# PC_ParallelPort.net
KiCad netlist of a schematic drawn in Altium Designer
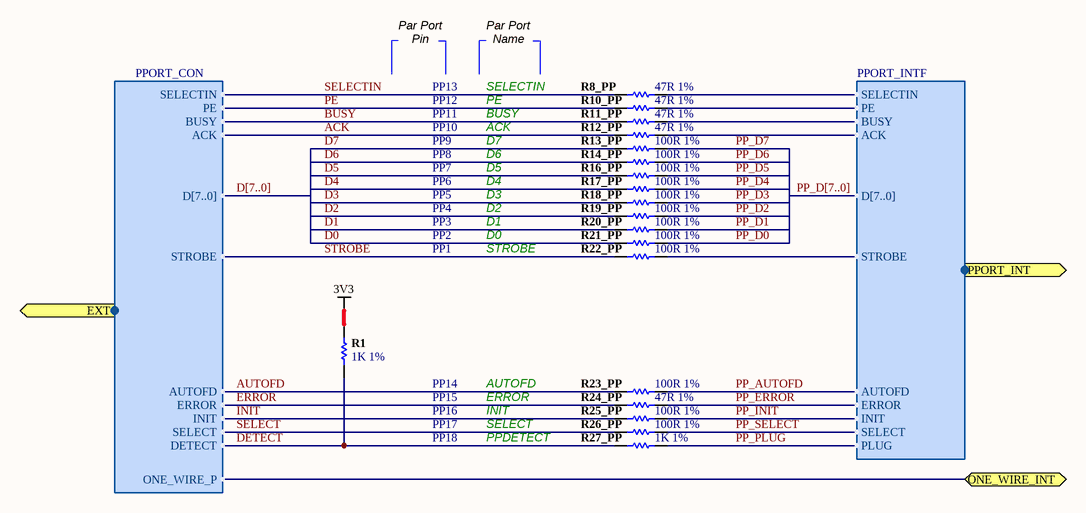
[diagram p0: PC_ParallelPort.SchDoc]

(export (version "E")
  (design (tool "Eeschema 10.0.6"))
  (components
    (comp (ref "R1")
      (value "1K 1%")
      (footprint "RESC1005-STAR")
      (description "Resistor, 1K 1% 0402 (1005)")
      (fields (field (name "TOLERANCE") "1 %"))
      (libsource (lib "AltiumDesignLibrary") (part "RES"))
    )
    (comp (ref "R8_PP")
      (value "47R 1%")
      (footprint "RESC1005-STAR")
      (description "Resistor, 47R 1% 0402 (1005)")
      (fields (field (name "TOLERANCE") "1 %"))
      (libsource (lib "AltiumDesignLibrary") (part "RES"))
    )
    (comp (ref "R10_PP")
      (value "47R 1%")
      (footprint "RESC1005-STAR")
      (description "Resistor, 47R 1% 0402 (1005)")
      (fields (field (name "TOLERANCE") "1 %"))
      (libsource (lib "AltiumDesignLibrary") (part "RES"))
    )
    (comp (ref "R11_PP")
      (value "47R 1%")
      (footprint "RESC1005-STAR")
      (description "Resistor, 47R 1% 0402 (1005)")
      (fields (field (name "TOLERANCE") "1 %"))
      (libsource (lib "AltiumDesignLibrary") (part "RES"))
    )
    (comp (ref "R12_PP")
      (value "47R 1%")
      (footprint "RESC1005-STAR")
      (description "Resistor, 47R 1% 0402 (1005)")
      (fields (field (name "TOLERANCE") "1 %"))
      (libsource (lib "AltiumDesignLibrary") (part "RES"))
    )
    (comp (ref "R13_PP")
      (value "100R 1%")
      (footprint "RESC1005-STAR")
      (description "Resistor, 100R 1% 0402 (1005)")
      (fields (field (name "TOLERANCE") "1 %"))
      (libsource (lib "AltiumDesignLibrary") (part "RES"))
    )
    (comp (ref "R14_PP")
      (value "100R 1%")
      (footprint "RESC1005-STAR")
      (description "Resistor, 100R 1% 0402 (1005)")
      (fields (field (name "TOLERANCE") "1 %"))
      (libsource (lib "AltiumDesignLibrary") (part "RES"))
    )
    (comp (ref "R16_PP")
      (value "100R 1%")
      (footprint "RESC1005-STAR")
      (description "Resistor, 100R 1% 0402 (1005)")
      (fields (field (name "TOLERANCE") "1 %"))
      (libsource (lib "AltiumDesignLibrary") (part "RES"))
    )
    (comp (ref "R17_PP")
      (value "100R 1%")
      (footprint "RESC1005-STAR")
      (description "Resistor, 100R 1% 0402 (1005)")
      (fields (field (name "TOLERANCE") "1 %"))
      (libsource (lib "AltiumDesignLibrary") (part "RES"))
    )
    (comp (ref "R18_PP")
      (value "100R 1%")
      (footprint "RESC1005-STAR")
      (description "Resistor, 100R 1% 0402 (1005)")
      (fields (field (name "TOLERANCE") "1 %"))
      (libsource (lib "AltiumDesignLibrary") (part "RES"))
    )
    (comp (ref "R19_PP")
      (value "100R 1%")
      (footprint "RESC1005-STAR")
      (description "Resistor, 100R 1% 0402 (1005)")
      (fields (field (name "TOLERANCE") "1 %"))
      (libsource (lib "AltiumDesignLibrary") (part "RES"))
    )
    (comp (ref "R20_PP")
      (value "100R 1%")
      (footprint "RESC1005-STAR")
      (description "Resistor, 100R 1% 0402 (1005)")
      (fields (field (name "TOLERANCE") "1 %"))
      (libsource (lib "AltiumDesignLibrary") (part "RES"))
    )
    (comp (ref "R21_PP")
      (value "100R 1%")
      (footprint "RESC1005-STAR")
      (description "Resistor, 100R 1% 0402 (1005)")
      (fields (field (name "TOLERANCE") "1 %"))
      (libsource (lib "AltiumDesignLibrary") (part "RES"))
    )
    (comp (ref "R22_PP")
      (value "100R 1%")
      (footprint "RESC1005-STAR")
      (description "Resistor, 100R 1% 0402 (1005)")
      (fields (field (name "TOLERANCE") "1 %"))
      (libsource (lib "AltiumDesignLibrary") (part "RES"))
    )
    (comp (ref "R23_PP")
      (value "100R 1%")
      (footprint "RESC1005-STAR")
      (description "Resistor, 100R 1% 0402 (1005)")
      (fields (field (name "TOLERANCE") "1 %"))
      (libsource (lib "AltiumDesignLibrary") (part "RES"))
    )
    (comp (ref "R24_PP")
      (value "47R 1%")
      (footprint "RESC1005-STAR")
      (description "Resistor, 47R 1% 0402 (1005)")
      (fields (field (name "TOLERANCE") "1 %"))
      (libsource (lib "AltiumDesignLibrary") (part "RES"))
    )
    (comp (ref "R25_PP")
      (value "100R 1%")
      (footprint "RESC1005-STAR")
      (description "Resistor, 100R 1% 0402 (1005)")
      (fields (field (name "TOLERANCE") "1 %"))
      (libsource (lib "AltiumDesignLibrary") (part "RES"))
    )
    (comp (ref "R26_PP")
      (value "100R 1%")
      (footprint "RESC1005-STAR")
      (description "Resistor, 100R 1% 0402 (1005)")
      (fields (field (name "TOLERANCE") "1 %"))
      (libsource (lib "AltiumDesignLibrary") (part "RES"))
    )
    (comp (ref "R27_PP")
      (value "1K 1%")
      (footprint "RESC1005-STAR")
      (description "Resistor, 1K 1% 0402 (1005)")
      (fields (field (name "TOLERANCE") "1 %"))
      (libsource (lib "AltiumDesignLibrary") (part "RES"))
    )
  )
  (nets
    (net (code "3") (name "/ACK") (class "Default")
      (node (ref "R12_PP") (pin "1") (pinfunction "1_1") (pintype "passive"))
    )
    (net (code "4") (name "/AUTOFD") (class "Default")
      (node (ref "R23_PP") (pin "2") (pinfunction "2_2") (pintype "passive"))
    )
    (net (code "5") (name "/BUSY") (class "Default")
      (node (ref "R11_PP") (pin "1") (pinfunction "1_1") (pintype "passive"))
    )
    (net (code "6") (name "/D0") (class "Default")
      (node (ref "R21_PP") (pin "2") (pinfunction "2_2") (pintype "passive"))
    )
    (net (code "7") (name "/D1") (class "Default")
      (node (ref "R20_PP") (pin "2") (pinfunction "2_2") (pintype "passive"))
    )
    (net (code "8") (name "/D2") (class "Default")
      (node (ref "R19_PP") (pin "2") (pinfunction "2_2") (pintype "passive"))
    )
    (net (code "9") (name "/D3") (class "Default")
      (node (ref "R18_PP") (pin "2") (pinfunction "2_2") (pintype "passive"))
    )
    (net (code "10") (name "/D4") (class "Default")
      (node (ref "R17_PP") (pin "2") (pinfunction "2_2") (pintype "passive"))
    )
    (net (code "11") (name "/D5") (class "Default")
      (node (ref "R16_PP") (pin "2") (pinfunction "2_2") (pintype "passive"))
    )
    (net (code "12") (name "/D6") (class "Default")
      (node (ref "R14_PP") (pin "2") (pinfunction "2_2") (pintype "passive"))
    )
    (net (code "13") (name "/D7") (class "Default")
      (node (ref "R13_PP") (pin "2") (pinfunction "2_2") (pintype "passive"))
    )
    (net (code "14") (name "/DETECT") (class "Default")
      (node (ref "R1") (pin "1") (pinfunction "1_1") (pintype "passive"))
      (node (ref "R27_PP") (pin "2") (pinfunction "2_2") (pintype "passive"))
    )
    (net (code "15") (name "/ERROR") (class "Default")
      (node (ref "R24_PP") (pin "1") (pinfunction "1_1") (pintype "passive"))
    )
    (net (code "17") (name "/INIT") (class "Default")
      (node (ref "R25_PP") (pin "2") (pinfunction "2_2") (pintype "passive"))
    )
    (net (code "19") (name "/PE") (class "Default")
      (node (ref "R10_PP") (pin "1") (pinfunction "1_1") (pintype "passive"))
    )
    (net (code "21") (name "/PP_AUTOFD") (class "Default")
      (node (ref "R23_PP") (pin "1") (pinfunction "1_1") (pintype "passive"))
    )
    (net (code "22") (name "/PP_D0") (class "Default")
      (node (ref "R21_PP") (pin "1") (pinfunction "1_1") (pintype "passive"))
    )
    (net (code "23") (name "/PP_D1") (class "Default")
      (node (ref "R20_PP") (pin "1") (pinfunction "1_1") (pintype "passive"))
    )
    (net (code "24") (name "/PP_D2") (class "Default")
      (node (ref "R19_PP") (pin "1") (pinfunction "1_1") (pintype "passive"))
    )
    (net (code "25") (name "/PP_D3") (class "Default")
      (node (ref "R18_PP") (pin "1") (pinfunction "1_1") (pintype "passive"))
    )
    (net (code "26") (name "/PP_D4") (class "Default")
      (node (ref "R17_PP") (pin "1") (pinfunction "1_1") (pintype "passive"))
    )
    (net (code "27") (name "/PP_D5") (class "Default")
      (node (ref "R16_PP") (pin "1") (pinfunction "1_1") (pintype "passive"))
    )
    (net (code "28") (name "/PP_D6") (class "Default")
      (node (ref "R14_PP") (pin "1") (pinfunction "1_1") (pintype "passive"))
    )
    (net (code "29") (name "/PP_D7") (class "Default")
      (node (ref "R13_PP") (pin "1") (pinfunction "1_1") (pintype "passive"))
    )
    (net (code "30") (name "/PP_ERROR") (class "Default")
      (node (ref "R24_PP") (pin "2") (pinfunction "2_2") (pintype "passive"))
    )
    (net (code "31") (name "/PP_INIT") (class "Default")
      (node (ref "R25_PP") (pin "1") (pinfunction "1_1") (pintype "passive"))
    )
    (net (code "32") (name "/PP_PLUG") (class "Default")
      (node (ref "R27_PP") (pin "1") (pinfunction "1_1") (pintype "passive"))
    )
    (net (code "33") (name "/PP_SELECT") (class "Default")
      (node (ref "R26_PP") (pin "1") (pinfunction "1_1") (pintype "passive"))
    )
    (net (code "34") (name "/SELECT") (class "Default")
      (node (ref "R26_PP") (pin "2") (pinfunction "2_2") (pintype "passive"))
    )
    (net (code "35") (name "/SELECTIN") (class "Default")
      (node (ref "R8_PP") (pin "1") (pinfunction "1_1") (pintype "passive"))
    )
    (net (code "36") (name "/STROBE") (class "Default")
      (node (ref "R22_PP") (pin "2") (pinfunction "2_2") (pintype "passive"))
    )
    (net (code "39") (name "3V3") (class "Default")
      (node (ref "R1") (pin "2") (pinfunction "2_2") (pintype "passive"))
    )
    (net (code "40") (name "unconnected-(R8_PP-Pad2)") (class "Default")
      (node (ref "R8_PP") (pin "2") (pinfunction "2_2") (pintype "passive"))
    )
    (net (code "41") (name "unconnected-(R10_PP-Pad2)") (class "Default")
      (node (ref "R10_PP") (pin "2") (pinfunction "2_2") (pintype "passive"))
    )
    (net (code "42") (name "unconnected-(R11_PP-Pad2)") (class "Default")
      (node (ref "R11_PP") (pin "2") (pinfunction "2_2") (pintype "passive"))
    )
    (net (code "43") (name "unconnected-(R12_PP-Pad2)") (class "Default")
      (node (ref "R12_PP") (pin "2") (pinfunction "2_2") (pintype "passive"))
    )
    (net (code "44") (name "unconnected-(R22_PP-Pad1)") (class "Default")
      (node (ref "R22_PP") (pin "1") (pinfunction "1_1") (pintype "passive"))
    )
  )
)
